# zx80_SD_12_smd_build002.net
KiCad netlist of a schematic drawn in EAGLE
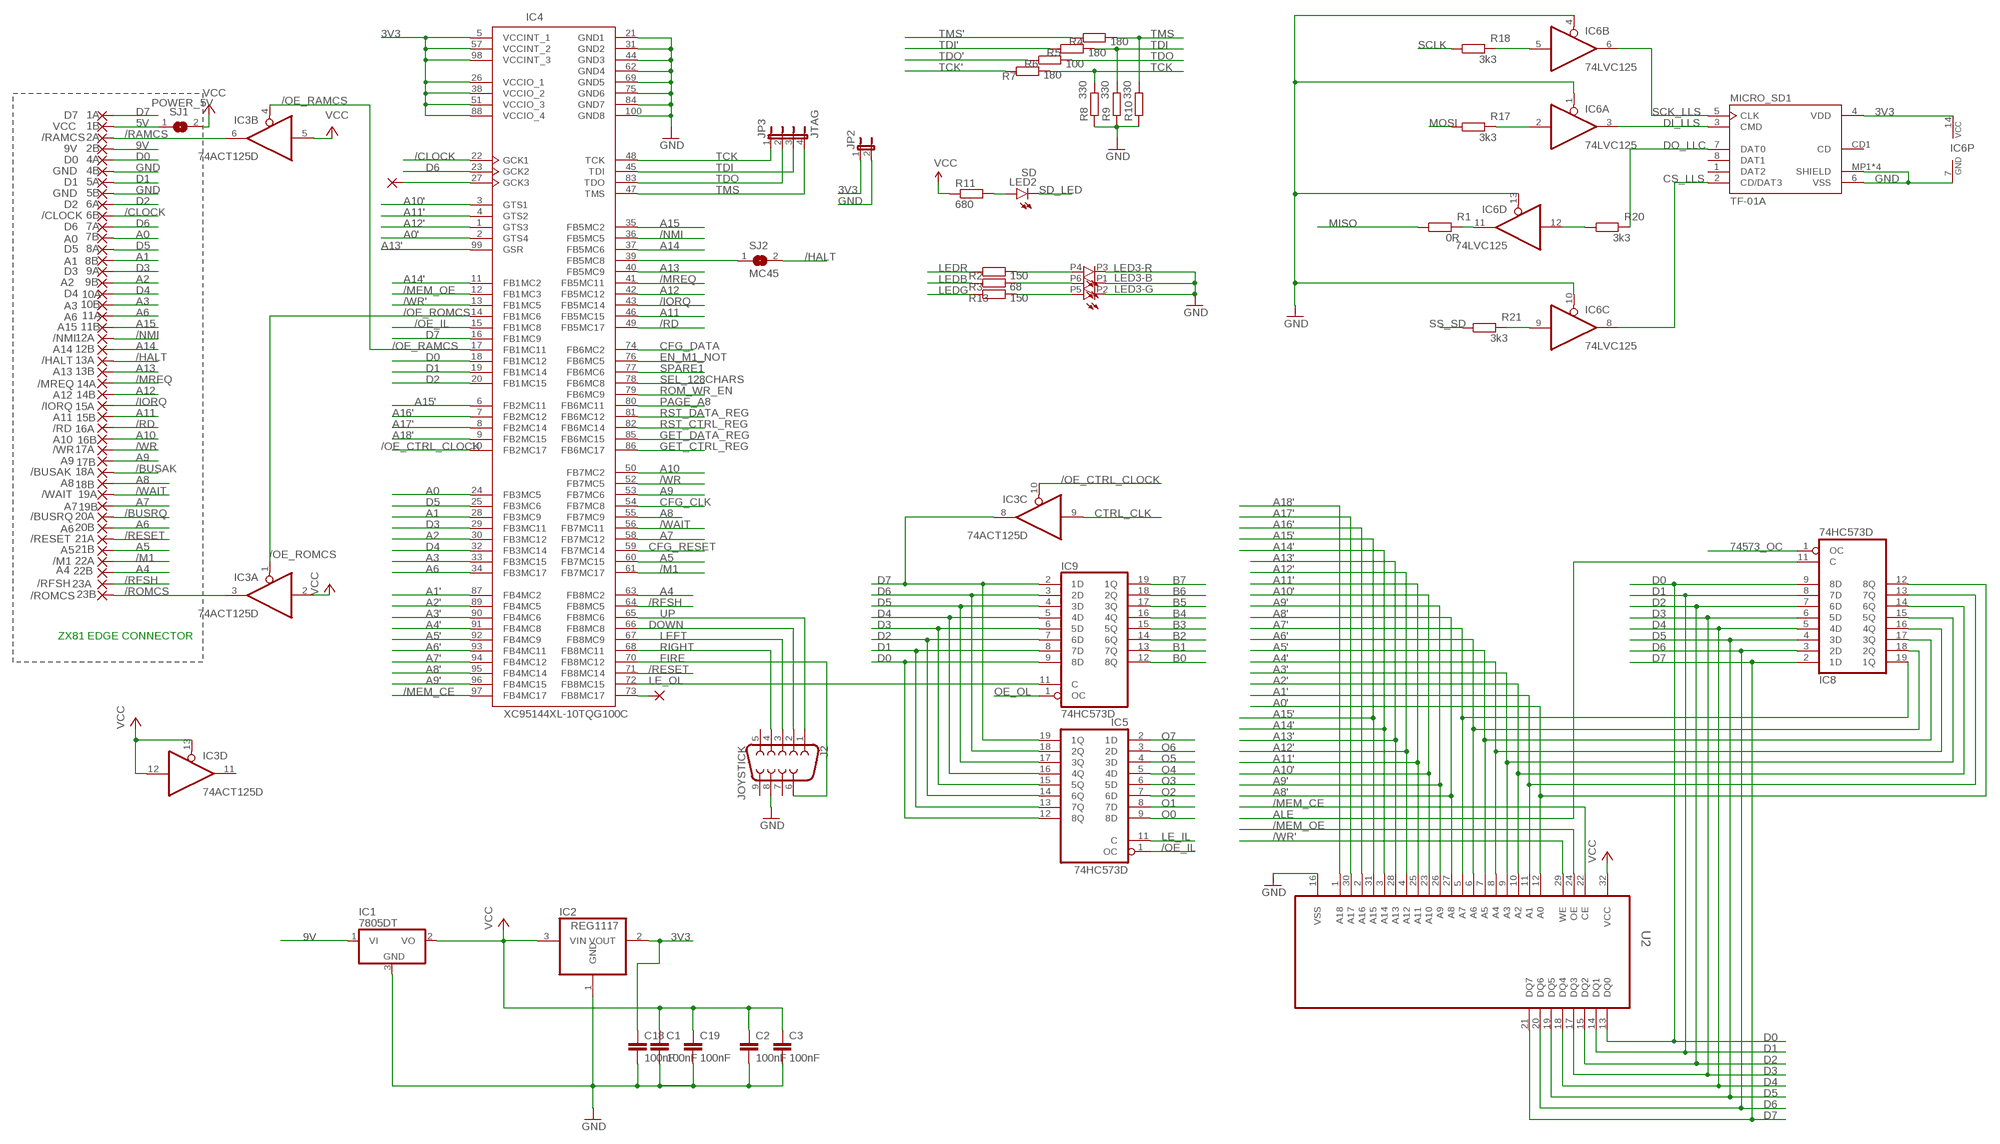
[diagram p0: schematic, sheet 1]
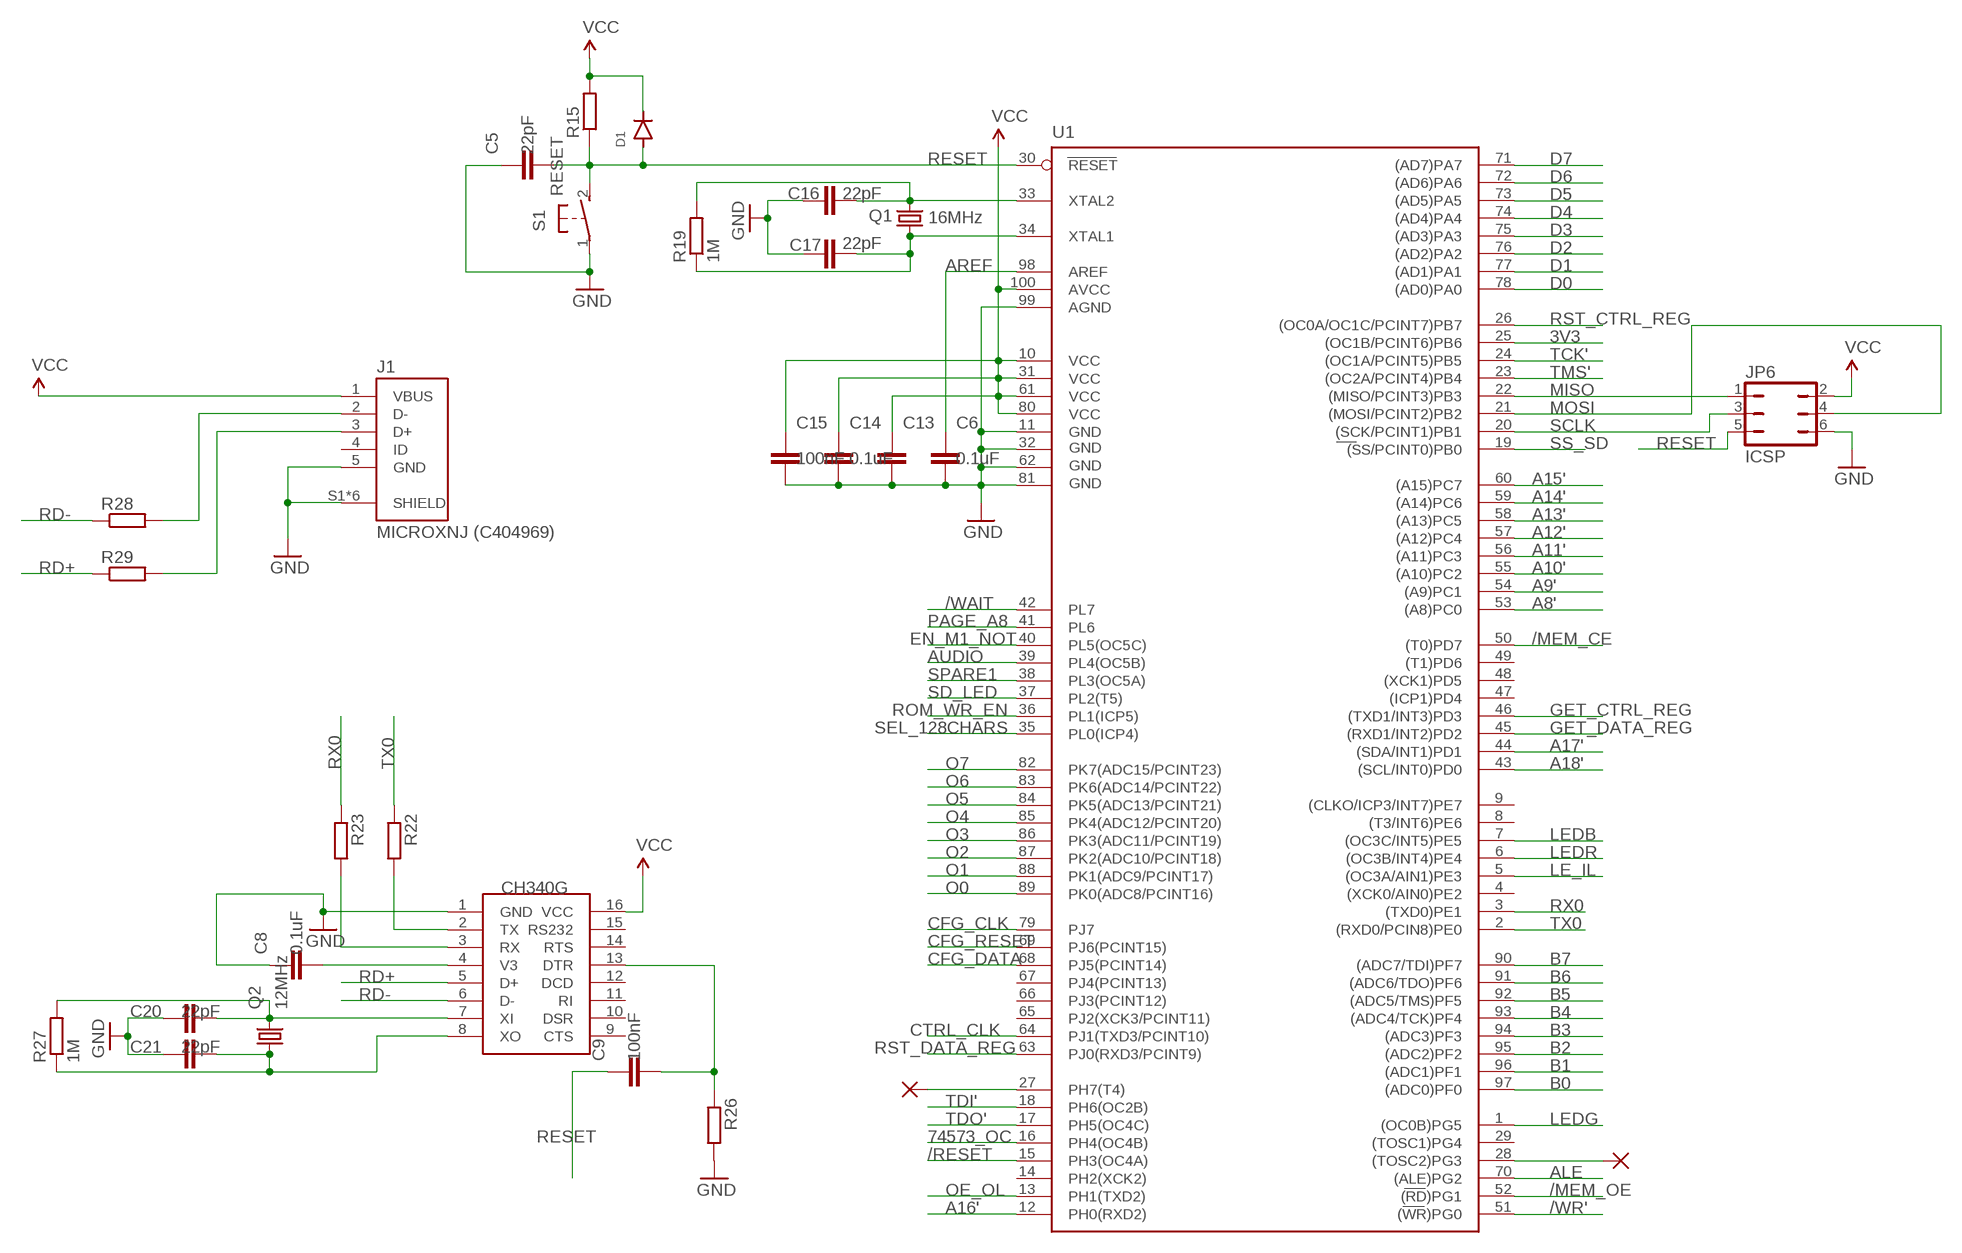
[diagram p1: schematic, sheet 2]

(export (version "E")
  (design (tool "Eeschema 10.0.6"))
  (components
    (comp (ref "C5")
      (value "22pF")
      (footprint "eagle-import:C0603")
      (libsource (lib "eagle-import") (part "C-EUC0603"))
    )
    (comp (ref "C6")
      (value "0.1uF")
      (footprint "eagle-import:C0603")
      (libsource (lib "eagle-import") (part "C-EUC0603"))
    )
    (comp (ref "C8")
      (value "0.1uF")
      (footprint "eagle-import:C0603")
      (libsource (lib "eagle-import") (part "C-EUC0603"))
    )
    (comp (ref "C9")
      (value "100nF")
      (footprint "eagle-import:C0603")
      (libsource (lib "eagle-import") (part "C-EUC0603"))
    )
    (comp (ref "C13")
      (value "0.1uF")
      (footprint "eagle-import:C0603")
      (libsource (lib "eagle-import") (part "C-EUC0603"))
    )
    (comp (ref "C14")
      (value "0.1uF")
      (footprint "eagle-import:C0603")
      (libsource (lib "eagle-import") (part "C-EUC0603"))
    )
    (comp (ref "C15")
      (value "100nF")
      (footprint "eagle-import:C0603")
      (libsource (lib "eagle-import") (part "C-EUC0603"))
    )
    (comp (ref "C16")
      (value "22pF")
      (footprint "eagle-import:C0603")
      (libsource (lib "eagle-import") (part "C-EUC0603"))
    )
    (comp (ref "C17")
      (value "22pF")
      (footprint "eagle-import:C0603")
      (libsource (lib "eagle-import") (part "C-EUC0603"))
    )
    (comp (ref "C20")
      (value "22pF")
      (footprint "eagle-import:C0603")
      (libsource (lib "eagle-import") (part "C-EUC0603"))
    )
    (comp (ref "C21")
      (value "22pF")
      (footprint "eagle-import:C0603")
      (libsource (lib "eagle-import") (part "C-EUC0603"))
    )
    (comp (ref "D1")
      (value "DIODE-SOD123")
      (footprint "eagle-import:SOD123")
      (libsource (lib "eagle-import") (part "DIODE-SOD123"))
    )
    (comp (ref "IC7")
      (value "CH340G")
      (footprint "eagle-import:SOIC16")
      (libsource (lib "eagle-import") (part "CH340G"))
    )
    (comp (ref "J1")
      (value "MICROXNJ (C404969)")
      (footprint "eagle-import:SHOUHAN_MICROXNJ")
      (fields (field (name "MF") "Shouhan") (field (name "MP") "MICROXNJ"))
      (libsource (lib "eagle-import") (part "MICROXNJ"))
    )
    (comp (ref "JP6")
      (value "ICSP")
      (footprint "eagle-import:JP3Q")
      (libsource (lib "eagle-import") (part "JP3Q"))
    )
    (comp (ref "PAD2")
      (value "1,6/0,8")
      (footprint "eagle-import:1,6_0,8")
      (libsource (lib "eagle-import") (part "1,6/0,8"))
    )
    (comp (ref "PAD3")
      (value "1,6/0,8")
      (footprint "eagle-import:1,6_0,8")
      (libsource (lib "eagle-import") (part "1,6/0,8"))
    )
    (comp (ref "Q1")
      (value "16MHz")
      (footprint "eagle-import:3.2X2.5_KX-7")
      (libsource (lib "eagle-import") (part "KX-7"))
    )
    (comp (ref "Q2")
      (value "12MHz")
      (footprint "eagle-import:3.2X2.5_KX-7")
      (libsource (lib "eagle-import") (part "KX-7"))
    )
    (comp (ref "R15")
      (value "R-EU_R0603")
      (footprint "eagle-import:R0603")
      (libsource (lib "eagle-import") (part "rcl_334_R-EU_R0603"))
    )
    (comp (ref "R19")
      (value "1M")
      (footprint "eagle-import:R0603")
      (libsource (lib "eagle-import") (part "rcl_334_R-EU_R0603"))
    )
    (comp (ref "R22")
      (value "1K")
      (footprint "eagle-import:R0603")
      (libsource (lib "eagle-import") (part "rcl_334_R-EU_R0603"))
    )
    (comp (ref "R23")
      (value "1K")
      (footprint "eagle-import:R0603")
      (libsource (lib "eagle-import") (part "rcl_334_R-EU_R0603"))
    )
    (comp (ref "R26")
      (value "1K")
      (footprint "eagle-import:R0603")
      (libsource (lib "eagle-import") (part "rcl_334_R-EU_R0603"))
    )
    (comp (ref "R27")
      (value "1M")
      (footprint "eagle-import:R0603")
      (libsource (lib "eagle-import") (part "rcl_334_R-EU_R0603"))
    )
    (comp (ref "R28")
      (value "22R")
      (footprint "eagle-import:R0603")
      (libsource (lib "eagle-import") (part "rcl_334_R-EU_R0603"))
    )
    (comp (ref "R29")
      (value "22R")
      (footprint "eagle-import:R0603")
      (libsource (lib "eagle-import") (part "rcl_334_R-EU_R0603"))
    )
    (comp (ref "S1")
      (value "RESET")
      (footprint "eagle-import:B3F-31XX")
      (fields (field (name "MPN") "B3F-3100"))
      (libsource (lib "eagle-import") (part "31-XX"))
    )
    (comp (ref "U1")
      (value "ATMEGA2560AU")
      (footprint "eagle-import:TQFP100")
      (libsource (lib "eagle-import") (part "ATMEGA2560AU"))
    )
    (comp (ref "1A")
      (value "D7")
      (footprint "eagle-import:EDGEPIN")
      (libsource (lib "eagle-import") (part "SMD2EDGEPIN"))
    )
    (comp (ref "1B")
      (value "VCC")
      (footprint "eagle-import:EDGEPIN")
      (libsource (lib "eagle-import") (part "SMD2EDGEPIN"))
    )
    (comp (ref "2A")
      (value "/RAMCS")
      (footprint "eagle-import:EDGEPIN")
      (libsource (lib "eagle-import") (part "SMD2EDGEPIN"))
    )
    (comp (ref "2B")
      (value "9V")
      (footprint "eagle-import:EDGEPIN")
      (libsource (lib "eagle-import") (part "SMD2EDGEPIN"))
    )
    (comp (ref "4A")
      (value "D0")
      (footprint "eagle-import:EDGEPIN")
      (libsource (lib "eagle-import") (part "SMD2EDGEPIN"))
    )
    (comp (ref "4B")
      (value "GND")
      (footprint "eagle-import:EDGEPIN")
      (libsource (lib "eagle-import") (part "SMD2EDGEPIN"))
    )
    (comp (ref "5A")
      (value "D1")
      (footprint "eagle-import:EDGEPIN")
      (libsource (lib "eagle-import") (part "SMD2EDGEPIN"))
    )
    (comp (ref "5B")
      (value "GND")
      (footprint "eagle-import:EDGEPIN")
      (libsource (lib "eagle-import") (part "SMD2EDGEPIN"))
    )
    (comp (ref "6A")
      (value "D2")
      (footprint "eagle-import:EDGEPIN")
      (libsource (lib "eagle-import") (part "SMD2EDGEPIN"))
    )
    (comp (ref "6B")
      (value "/CLOCK")
      (footprint "eagle-import:EDGEPIN")
      (libsource (lib "eagle-import") (part "SMD2EDGEPIN"))
    )
    (comp (ref "7A")
      (value "D6")
      (footprint "eagle-import:EDGEPIN")
      (libsource (lib "eagle-import") (part "SMD2EDGEPIN"))
    )
    (comp (ref "7B")
      (value "A0")
      (footprint "eagle-import:EDGEPIN")
      (libsource (lib "eagle-import") (part "SMD2EDGEPIN"))
    )
    (comp (ref "8A")
      (value "D5")
      (footprint "eagle-import:EDGEPIN")
      (libsource (lib "eagle-import") (part "SMD2EDGEPIN"))
    )
    (comp (ref "8B")
      (value "A1")
      (footprint "eagle-import:EDGEPIN")
      (libsource (lib "eagle-import") (part "SMD2EDGEPIN"))
    )
    (comp (ref "9A")
      (value "D3")
      (footprint "eagle-import:EDGEPIN")
      (libsource (lib "eagle-import") (part "SMD2EDGEPIN"))
    )
    (comp (ref "9B")
      (value "A2")
      (footprint "eagle-import:EDGEPIN")
      (libsource (lib "eagle-import") (part "SMD2EDGEPIN"))
    )
    (comp (ref "10A")
      (value "D4")
      (footprint "eagle-import:EDGEPIN")
      (libsource (lib "eagle-import") (part "SMD2EDGEPIN"))
    )
    (comp (ref "10B")
      (value "A3")
      (footprint "eagle-import:EDGEPIN")
      (libsource (lib "eagle-import") (part "SMD2EDGEPIN"))
    )
    (comp (ref "11A")
      (value "A6")
      (footprint "eagle-import:EDGEPIN")
      (libsource (lib "eagle-import") (part "SMD2EDGEPIN"))
    )
    (comp (ref "11B")
      (value "A15")
      (footprint "eagle-import:EDGEPIN")
      (libsource (lib "eagle-import") (part "SMD2EDGEPIN"))
    )
    (comp (ref "12A")
      (value "/NMI")
      (footprint "eagle-import:EDGEPIN")
      (libsource (lib "eagle-import") (part "SMD2EDGEPIN"))
    )
    (comp (ref "12B")
      (value "A14")
      (footprint "eagle-import:EDGEPIN")
      (libsource (lib "eagle-import") (part "SMD2EDGEPIN"))
    )
    (comp (ref "13A")
      (value "/HALT")
      (footprint "eagle-import:EDGEPIN")
      (libsource (lib "eagle-import") (part "SMD2EDGEPIN"))
    )
    (comp (ref "13B")
      (value "A13")
      (footprint "eagle-import:EDGEPIN")
      (libsource (lib "eagle-import") (part "SMD2EDGEPIN"))
    )
    (comp (ref "14A")
      (value "/MREQ")
      (footprint "eagle-import:EDGEPIN")
      (libsource (lib "eagle-import") (part "SMD2EDGEPIN"))
    )
    (comp (ref "14B")
      (value "A12")
      (footprint "eagle-import:EDGEPIN")
      (libsource (lib "eagle-import") (part "SMD2EDGEPIN"))
    )
    (comp (ref "15A")
      (value "/IORQ")
      (footprint "eagle-import:EDGEPIN")
      (libsource (lib "eagle-import") (part "SMD2EDGEPIN"))
    )
    (comp (ref "15B")
      (value "A11")
      (footprint "eagle-import:EDGEPIN")
      (libsource (lib "eagle-import") (part "SMD2EDGEPIN"))
    )
    (comp (ref "16A")
      (value "/RD")
      (footprint "eagle-import:EDGEPIN")
      (libsource (lib "eagle-import") (part "SMD2EDGEPIN"))
    )
    (comp (ref "16B")
      (value "A10")
      (footprint "eagle-import:EDGEPIN")
      (libsource (lib "eagle-import") (part "SMD2EDGEPIN"))
    )
    (comp (ref "17A")
      (value "/WR")
      (footprint "eagle-import:EDGEPIN")
      (libsource (lib "eagle-import") (part "SMD2EDGEPIN"))
    )
    (comp (ref "17B")
      (value "A9")
      (footprint "eagle-import:EDGEPIN")
      (libsource (lib "eagle-import") (part "SMD2EDGEPIN"))
    )
    (comp (ref "18A")
      (value "/BUSAK")
      (footprint "eagle-import:EDGEPIN")
      (libsource (lib "eagle-import") (part "SMD2EDGEPIN"))
    )
    (comp (ref "18B")
      (value "A8")
      (footprint "eagle-import:EDGEPIN")
      (libsource (lib "eagle-import") (part "SMD2EDGEPIN"))
    )
    (comp (ref "19A")
      (value "/WAIT")
      (footprint "eagle-import:EDGEPIN")
      (libsource (lib "eagle-import") (part "SMD2EDGEPIN"))
    )
    (comp (ref "19B")
      (value "A7")
      (footprint "eagle-import:EDGEPIN")
      (libsource (lib "eagle-import") (part "SMD2EDGEPIN"))
    )
    (comp (ref "20A")
      (value "/BUSRQ")
      (footprint "eagle-import:EDGEPIN")
      (libsource (lib "eagle-import") (part "SMD2EDGEPIN"))
    )
    (comp (ref "20B")
      (value "A6")
      (footprint "eagle-import:EDGEPIN")
      (libsource (lib "eagle-import") (part "SMD2EDGEPIN"))
    )
    (comp (ref "21A")
      (value "/RESET")
      (footprint "eagle-import:EDGEPIN")
      (libsource (lib "eagle-import") (part "SMD2EDGEPIN"))
    )
    (comp (ref "21B")
      (value "A5")
      (footprint "eagle-import:EDGEPIN")
      (libsource (lib "eagle-import") (part "SMD2EDGEPIN"))
    )
    (comp (ref "22A")
      (value "/M1")
      (footprint "eagle-import:EDGEPIN")
      (libsource (lib "eagle-import") (part "SMD2EDGEPIN"))
    )
    (comp (ref "22B")
      (value "A4")
      (footprint "eagle-import:EDGEPIN")
      (libsource (lib "eagle-import") (part "SMD2EDGEPIN"))
    )
    (comp (ref "23A")
      (value "/RFSH")
      (footprint "eagle-import:EDGEPIN")
      (libsource (lib "eagle-import") (part "SMD2EDGEPIN"))
    )
    (comp (ref "23B")
      (value "/ROMCS")
      (footprint "eagle-import:EDGEPIN")
      (libsource (lib "eagle-import") (part "SMD2EDGEPIN"))
    )
    (comp (ref "C1")
      (value "100nF")
      (footprint "eagle-import:C0603")
      (libsource (lib "eagle-import") (part "C-EUC0603"))
    )
    (comp (ref "C2")
      (value "100nF")
      (footprint "eagle-import:C0603")
      (libsource (lib "eagle-import") (part "C-EUC0603"))
    )
    (comp (ref "C3")
      (value "100nF")
      (footprint "eagle-import:C0603")
      (libsource (lib "eagle-import") (part "C-EUC0603"))
    )
    (comp (ref "C18")
      (value "100nF")
      (footprint "eagle-import:C0603")
      (libsource (lib "eagle-import") (part "C-EUC0603"))
    )
    (comp (ref "C19")
      (value "100nF")
      (footprint "eagle-import:C0603")
      (libsource (lib "eagle-import") (part "C-EUC0603"))
    )
    (comp (ref "IC1")
      (value "7805DT")
      (footprint "eagle-import:TO252")
      (libsource (lib "eagle-import") (part "78DT05"))
    )
    (comp (ref "IC2")
      (value "REG1117")
      (footprint "eagle-import:SOT223")
      (libsource (lib "eagle-import") (part "REG1117"))
    )
    (comp (ref "IC3")
      (value "74ACT125D")
      (footprint "eagle-import:SO14")
      (libsource (lib "eagle-import") (part "74125DACT"))
    )
    (comp (ref "IC4")
      (value "XC95144XL-10TQG100C")
      (footprint "eagle-import:TQFP100")
      (fields (field (name "MF") "Xilinx Inc."))
      (libsource (lib "eagle-import") (part "XC95144XL-10TQG100C"))
    )
    (comp (ref "IC5")
      (value "74HC573D")
      (footprint "eagle-import:SO20W")
      (libsource (lib "eagle-import") (part "74573DHC"))
    )
    (comp (ref "IC6")
      (value "74LVC125")
      (footprint "eagle-import:SO14")
      (libsource (lib "eagle-import") (part "74125DLS"))
    )
    (comp (ref "IC8")
      (value "74HC573D")
      (footprint "eagle-import:SO20W")
      (libsource (lib "eagle-import") (part "74573DHC"))
    )
    (comp (ref "IC9")
      (value "74HC573D")
      (footprint "eagle-import:SO20W")
      (libsource (lib "eagle-import") (part "74573DHC"))
    )
    (comp (ref "J2")
      (value "JOYSTICK")
      (footprint "eagle-import:DB9_MALE")
      (libsource (lib "eagle-import") (part "DB9MALE"))
    )
    (comp (ref "JP2")
      (value "JP1E")
      (footprint "eagle-import:JP1")
      (libsource (lib "eagle-import") (part "JP1E"))
    )
    (comp (ref "JP3")
      (value "JTAG")
      (footprint "eagle-import:JP4")
      (libsource (lib "eagle-import") (part "JP4E"))
    )
    (comp (ref "LED2")
      (value "SD")
      (footprint "eagle-import:CHIPLED_0603")
      (libsource (lib "eagle-import") (part "LEDCHIPLED_0603"))
    )
    (comp (ref "LED3")
      (value "STATUS")
      (footprint "eagle-import:3535-PLCC6")
      (libsource (lib "eagle-import") (part "3535RGB3535RGB"))
    )
    (comp (ref "MICRO_SD1")
      (value "TF-01A")
      (footprint "eagle-import:TF-01A")
      (fields (field (name "MF") "HRO Electronics Co., Ltd."))
      (libsource (lib "eagle-import") (part "TF-01A"))
    )
    (comp (ref "PAD1")
      (value "1,6/0,8")
      (footprint "eagle-import:1,6_0,8")
      (libsource (lib "eagle-import") (part "1,6/0,8"))
    )
    (comp (ref "PAD6")
      (value "P73")
      (footprint "eagle-import:1,6_0,8")
      (libsource (lib "eagle-import") (part "1,6/0,8"))
    )
    (comp (ref "R1")
      (value "0R")
      (footprint "eagle-import:R0603")
      (libsource (lib "eagle-import") (part "R-EU_R0603"))
    )
    (comp (ref "R2")
      (value "150")
      (footprint "eagle-import:R0603")
      (libsource (lib "eagle-import") (part "rcl_334_R-EU_R0603"))
    )
    (comp (ref "R3")
      (value "68")
      (footprint "eagle-import:R0603")
      (libsource (lib "eagle-import") (part "rcl_334_R-EU_R0603"))
    )
    (comp (ref "R4")
      (value "180")
      (footprint "eagle-import:R0603")
      (libsource (lib "eagle-import") (part "rcl_334_R-EU_R0603"))
    )
    (comp (ref "R5")
      (value "180")
      (footprint "eagle-import:R0603")
      (libsource (lib "eagle-import") (part "rcl_334_R-EU_R0603"))
    )
    (comp (ref "R6")
      (value "100")
      (footprint "eagle-import:R0603")
      (libsource (lib "eagle-import") (part "rcl_334_R-EU_R0603"))
    )
    (comp (ref "R7")
      (value "180")
      (footprint "eagle-import:R0603")
      (libsource (lib "eagle-import") (part "rcl_334_R-EU_R0603"))
    )
    (comp (ref "R8")
      (value "330")
      (footprint "eagle-import:R0603")
      (libsource (lib "eagle-import") (part "rcl_334_R-EU_R0603"))
    )
    (comp (ref "R9")
      (value "330")
      (footprint "eagle-import:R0603")
      (libsource (lib "eagle-import") (part "rcl_334_R-EU_R0603"))
    )
    (comp (ref "R10")
      (value "330")
      (footprint "eagle-import:R0603")
      (libsource (lib "eagle-import") (part "rcl_334_R-EU_R0603"))
    )
    (comp (ref "R11")
      (value "680")
      (footprint "eagle-import:R0603")
      (libsource (lib "eagle-import") (part "R-EU_R0603"))
    )
    (comp (ref "R13")
      (value "150")
      (footprint "eagle-import:R0603")
      (libsource (lib "eagle-import") (part "rcl_334_R-EU_R0603"))
    )
    (comp (ref "R17")
      (value "3k3")
      (footprint "eagle-import:R0603")
      (libsource (lib "eagle-import") (part "R-EU_R0603"))
    )
    (comp (ref "R18")
      (value "3k3")
      (footprint "eagle-import:R0603")
      (libsource (lib "eagle-import") (part "R-EU_R0603"))
    )
    (comp (ref "R20")
      (value "3k3")
      (footprint "eagle-import:R0603")
      (libsource (lib "eagle-import") (part "R-EU_R0603"))
    )
    (comp (ref "R21")
      (value "3k3")
      (footprint "eagle-import:R0603")
      (libsource (lib "eagle-import") (part "R-EU_R0603"))
    )
    (comp (ref "SJ1")
      (value "POWER_5V")
      (footprint "eagle-import:SJ")
      (libsource (lib "eagle-import") (part "SJ"))
    )
    (comp (ref "SJ2")
      (value "MC45")
      (footprint "eagle-import:SJ")
      (libsource (lib "eagle-import") (part "SJ"))
    )
    (comp (ref "U2")
      (value "AS6C4008-55SINSOP5")
      (footprint "eagle-import:SOP32-5")
      (libsource (lib "eagle-import") (part "AS6C4008-55SINSOP5"))
    )
  )
  (nets
    (net (code "1") (name "3V3") (class "Default")
      (node (ref "C18") (pin "1") (pinfunction "1_1") (pintype "passive"))
      (node (ref "IC2") (pin "2") (pinfunction "VOUT_2") (pintype "output"))
      (node (ref "IC4") (pin "26") (pinfunction "VCCIO_1_26") (pintype "power_in"))
      (node (ref "IC4") (pin "38") (pinfunction "VCCIO_2_38") (pintype "power_in"))
      (node (ref "IC4") (pin "5") (pinfunction "VCCINT_1_5") (pintype "power_in"))
      (node (ref "IC4") (pin "51") (pinfunction "VCCIO_3_51") (pintype "power_in"))
      (node (ref "IC4") (pin "57") (pinfunction "VCCINT_2_57") (pintype "power_in"))
      (node (ref "IC4") (pin "88") (pinfunction "VCCIO_4_88") (pintype "power_in"))
      (node (ref "IC4") (pin "98") (pinfunction "VCCINT_3_98") (pintype "power_in"))
      (node (ref "IC6") (pin "14") (pinfunction "VCC_14") (pintype "power_in"))
      (node (ref "JP2") (pin "1") (pinfunction "1_1") (pintype "passive"))
      (node (ref "MICRO_SD1") (pin "4") (pinfunction "VDD_4") (pintype "power_in"))
      (node (ref "U1") (pin "25") (pinfunction "(OC1B/PCINT6)PB6_25") (pintype "bidirectional"))
    )
    (net (code "2") (name "5V") (class "Default")
      (node (ref "1B") (pin "1") (pinfunction "P_1") (pintype "passive"))
      (node (ref "SJ1") (pin "1") (pinfunction "1_1") (pintype "passive"))
    )
    (net (code "3") (name "9V") (class "Default")
      (node (ref "2B") (pin "1") (pinfunction "P_1") (pintype "passive"))
      (node (ref "IC1") (pin "1") (pinfunction "VI_1") (pintype "input"))
    )
    (net (code "4") (name "74573_OC") (class "Default")
      (node (ref "IC8") (pin "1") (pinfunction "OC_1") (pintype "input"))
      (node (ref "U1") (pin "16") (pinfunction "PH4(OC4B)_16") (pintype "bidirectional"))
    )
    (net (code "5") (name "A0") (class "Default")
      (node (ref "7B") (pin "1") (pinfunction "P_1") (pintype "passive"))
      (node (ref "IC4") (pin "24") (pinfunction "FB3MC5_24") (pintype "bidirectional"))
    )
    (net (code "6") (name "A0'") (class "Default")
      (node (ref "IC4") (pin "2") (pinfunction "GTS4_2") (pintype "bidirectional"))
      (node (ref "IC8") (pin "12") (pinfunction "8Q_12") (pintype "tri_state"))
      (node (ref "U2") (pin "12") (pinfunction "A0_12") (pintype "input"))
    )
    (net (code "7") (name "A1") (class "Default")
      (node (ref "8B") (pin "1") (pinfunction "P_1") (pintype "passive"))
      (node (ref "IC4") (pin "28") (pinfunction "FB3MC9_28") (pintype "bidirectional"))
    )
    (net (code "8") (name "A1'") (class "Default")
      (node (ref "IC4") (pin "87") (pinfunction "FB4MC2_87") (pintype "bidirectional"))
      (node (ref "IC8") (pin "13") (pinfunction "7Q_13") (pintype "tri_state"))
      (node (ref "U2") (pin "11") (pinfunction "A1_11") (pintype "input"))
    )
    (net (code "9") (name "A2") (class "Default")
      (node (ref "9B") (pin "1") (pinfunction "P_1") (pintype "passive"))
      (node (ref "IC4") (pin "30") (pinfunction "FB3MC12_30") (pintype "bidirectional"))
    )
    (net (code "10") (name "A2'") (class "Default")
      (node (ref "IC4") (pin "89") (pinfunction "FB4MC5_89") (pintype "bidirectional"))
      (node (ref "IC8") (pin "14") (pinfunction "6Q_14") (pintype "tri_state"))
      (node (ref "U2") (pin "10") (pinfunction "A2_10") (pintype "input"))
    )
    (net (code "11") (name "A3") (class "Default")
      (node (ref "10B") (pin "1") (pinfunction "P_1") (pintype "passive"))
      (node (ref "IC4") (pin "33") (pinfunction "FB3MC15_33") (pintype "bidirectional"))
    )
    (net (code "12") (name "A3'") (class "Default")
      (node (ref "IC4") (pin "90") (pinfunction "FB4MC6_90") (pintype "bidirectional"))
      (node (ref "IC8") (pin "15") (pinfunction "5Q_15") (pintype "tri_state"))
      (node (ref "U2") (pin "9") (pinfunction "A3_9") (pintype "input"))
    )
    (net (code "13") (name "A4") (class "Default")
      (node (ref "22B") (pin "1") (pinfunction "P_1") (pintype "passive"))
      (node (ref "IC4") (pin "63") (pinfunction "FB8MC2_63") (pintype "bidirectional"))
    )
    (net (code "14") (name "A4'") (class "Default")
      (node (ref "IC4") (pin "91") (pinfunction "FB4MC8_91") (pintype "bidirectional"))
      (node (ref "IC8") (pin "16") (pinfunction "4Q_16") (pintype "tri_state"))
      (node (ref "U2") (pin "8") (pinfunction "A4_8") (pintype "input"))
    )
    (net (code "15") (name "A5") (class "Default")
      (node (ref "21B") (pin "1") (pinfunction "P_1") (pintype "passive"))
      (node (ref "IC4") (pin "60") (pinfunction "FB7MC15_60") (pintype "bidirectional"))
    )
    (net (code "16") (name "A5'") (class "Default")
      (node (ref "IC4") (pin "92") (pinfunction "FB4MC9_92") (pintype "bidirectional"))
      (node (ref "IC8") (pin "17") (pinfunction "3Q_17") (pintype "tri_state"))
      (node (ref "U2") (pin "7") (pinfunction "A5_7") (pintype "input"))
    )
    (net (code "17") (name "A6") (class "Default")
      (node (ref "11A") (pin "1") (pinfunction "P_1") (pintype "passive"))
      (node (ref "20B") (pin "1") (pinfunction "P_1") (pintype "passive"))
      (node (ref "IC4") (pin "34") (pinfunction "FB3MC17_34") (pintype "bidirectional"))
    )
    (net (code "18") (name "A6'") (class "Default")
      (node (ref "IC4") (pin "93") (pinfunction "FB4MC11_93") (pintype "bidirectional"))
      (node (ref "IC8") (pin "18") (pinfunction "2Q_18") (pintype "tri_state"))
      (node (ref "U2") (pin "6") (pinfunction "A6_6") (pintype "input"))
    )
    (net (code "19") (name "A7") (class "Default")
      (node (ref "19B") (pin "1") (pinfunction "P_1") (pintype "passive"))
      (node (ref "IC4") (pin "58") (pinfunction "FB7MC12_58") (pintype "bidirectional"))
    )
    (net (code "20") (name "A7'") (class "Default")
      (node (ref "IC4") (pin "94") (pinfunction "FB4MC12_94") (pintype "bidirectional"))
      (node (ref "IC8") (pin "19") (pinfunction "1Q_19") (pintype "tri_state"))
      (node (ref "U2") (pin "5") (pinfunction "A7_5") (pintype "input"))
    )
    (net (code "21") (name "A8") (class "Default")
      (node (ref "18B") (pin "1") (pinfunction "P_1") (pintype "passive"))
      (node (ref "IC4") (pin "55") (pinfunction "FB7MC9_55") (pintype "bidirectional"))
    )
    (net (code "22") (name "A8'") (class "Default")
      (node (ref "IC4") (pin "95") (pinfunction "FB4MC14_95") (pintype "bidirectional"))
      (node (ref "U1") (pin "53") (pinfunction "(A8)PC0_53") (pintype "bidirectional"))
      (node (ref "U2") (pin "27") (pinfunction "A8_27") (pintype "input"))
    )
    (net (code "23") (name "A9") (class "Default")
      (node (ref "17B") (pin "1") (pinfunction "P_1") (pintype "passive"))
      (node (ref "IC4") (pin "53") (pinfunction "FB7MC6_53") (pintype "bidirectional"))
    )
    (net (code "24") (name "A9'") (class "Default")
      (node (ref "IC4") (pin "96") (pinfunction "FB4MC15_96") (pintype "bidirectional"))
      (node (ref "U1") (pin "54") (pinfunction "(A9)PC1_54") (pintype "bidirectional"))
      (node (ref "U2") (pin "26") (pinfunction "A9_26") (pintype "input"))
    )
    (net (code "25") (name "A10") (class "Default")
      (node (ref "16B") (pin "1") (pinfunction "P_1") (pintype "passive"))
      (node (ref "IC4") (pin "50") (pinfunction "FB7MC2_50") (pintype "bidirectional"))
    )
    (net (code "26") (name "A10'") (class "Default")
      (node (ref "IC4") (pin "3") (pinfunction "GTS1_3") (pintype "bidirectional"))
      (node (ref "U1") (pin "55") (pinfunction "(A10)PC2_55") (pintype "bidirectional"))
      (node (ref "U2") (pin "23") (pinfunction "A10_23") (pintype "input"))
    )
    (net (code "27") (name "A11") (class "Default")
      (node (ref "15B") (pin "1") (pinfunction "P_1") (pintype "passive"))
      (node (ref "IC4") (pin "46") (pinfunction "FB5MC15_46") (pintype "bidirectional"))
    )
    (net (code "28") (name "A11'") (class "Default")
      (node (ref "IC4") (pin "4") (pinfunction "GTS2_4") (pintype "bidirectional"))
      (node (ref "U1") (pin "56") (pinfunction "(A11)PC3_56") (pintype "bidirectional"))
      (node (ref "U2") (pin "25") (pinfunction "A11_25") (pintype "input"))
    )
    (net (code "29") (name "A12") (class "Default")
      (node (ref "14B") (pin "1") (pinfunction "P_1") (pintype "passive"))
      (node (ref "IC4") (pin "42") (pinfunction "FB5MC12_42") (pintype "bidirectional"))
    )
    (net (code "30") (name "A12'") (class "Default")
      (node (ref "IC4") (pin "1") (pinfunction "GTS3_1") (pintype "bidirectional"))
      (node (ref "U1") (pin "57") (pinfunction "(A12)PC4_57") (pintype "bidirectional"))
      (node (ref "U2") (pin "4") (pinfunction "A12_4") (pintype "input"))
    )
    (net (code "31") (name "A13") (class "Default")
      (node (ref "13B") (pin "1") (pinfunction "P_1") (pintype "passive"))
      (node (ref "IC4") (pin "40") (pinfunction "FB5MC9_40") (pintype "bidirectional"))
    )
    (net (code "32") (name "A13'") (class "Default")
      (node (ref "IC4") (pin "99") (pinfunction "GSR_99") (pintype "bidirectional"))
      (node (ref "U1") (pin "58") (pinfunction "(A13)PC5_58") (pintype "bidirectional"))
      (node (ref "U2") (pin "28") (pinfunction "A13_28") (pintype "input"))
    )
    (net (code "33") (name "A14") (class "Default")
      (node (ref "12B") (pin "1") (pinfunction "P_1") (pintype "passive"))
      (node (ref "IC4") (pin "37") (pinfunction "FB5MC6_37") (pintype "bidirectional"))
    )
    (net (code "34") (name "A14'") (class "Default")
      (node (ref "IC4") (pin "11") (pinfunction "FB1MC2_11") (pintype "bidirectional"))
      (node (ref "U1") (pin "59") (pinfunction "(A14)PC6_59") (pintype "bidirectional"))
      (node (ref "U2") (pin "3") (pinfunction "A14_3") (pintype "input"))
    )
    (net (code "35") (name "A15") (class "Default")
      (node (ref "11B") (pin "1") (pinfunction "P_1") (pintype "passive"))
      (node (ref "IC4") (pin "35") (pinfunction "FB5MC2_35") (pintype "bidirectional"))
    )
    (net (code "36") (name "A15'") (class "Default")
      (node (ref "IC4") (pin "6") (pinfunction "FB2MC11_6") (pintype "bidirectional"))
      (node (ref "U1") (pin "60") (pinfunction "(A15)PC7_60") (pintype "bidirectional"))
      (node (ref "U2") (pin "31") (pinfunction "A15_31") (pintype "input"))
    )
    (net (code "37") (name "A16'") (class "Default")
      (node (ref "IC4") (pin "7") (pinfunction "FB2MC12_7") (pintype "bidirectional"))
      (node (ref "U1") (pin "12") (pinfunction "PH0(RXD2)_12") (pintype "bidirectional"))
      (node (ref "U2") (pin "2") (pinfunction "A16_2") (pintype "input"))
    )
    (net (code "38") (name "A17'") (class "Default")
      (node (ref "IC4") (pin "8") (pinfunction "FB2MC14_8") (pintype "bidirectional"))
      (node (ref "U1") (pin "44") (pinfunction "(SDA/INT1)PD1_44") (pintype "bidirectional"))
      (node (ref "U2") (pin "30") (pinfunction "A17_30") (pintype "input"))
    )
    (net (code "39") (name "A18'") (class "Default")
      (node (ref "IC4") (pin "9") (pinfunction "FB2MC15_9") (pintype "bidirectional"))
      (node (ref "U1") (pin "43") (pinfunction "(SCL/INT0)PD0_43") (pintype "bidirectional"))
      (node (ref "U2") (pin "1") (pinfunction "A18_1") (pintype "input"))
    )
    (net (code "40") (name "ALE") (class "Default")
      (node (ref "IC8") (pin "11") (pinfunction "C_11") (pintype "input"))
      (node (ref "U1") (pin "70") (pinfunction "(ALE)PG2_70") (pintype "bidirectional"))
    )
    (net (code "41") (name "AREF") (class "Default")
      (node (ref "C6") (pin "1") (pinfunction "1_1") (pintype "passive"))
      (node (ref "U1") (pin "98") (pinfunction "AREF_98") (pintype "bidirectional"))
    )
    (net (code "42") (name "AUDIO") (class "Default")
      (node (ref "U1") (pin "39") (pinfunction "PL4(OC5B)_39") (pintype "bidirectional"))
    )
    (net (code "43") (name "B0") (class "Default")
      (node (ref "IC9") (pin "12") (pinfunction "8Q_12") (pintype "tri_state"))
      (node (ref "U1") (pin "97") (pinfunction "(ADC0)PF0_97") (pintype "bidirectional"))
    )
    (net (code "44") (name "B1") (class "Default")
      (node (ref "IC9") (pin "13") (pinfunction "7Q_13") (pintype "tri_state"))
      (node (ref "U1") (pin "96") (pinfunction "(ADC1)PF1_96") (pintype "bidirectional"))
    )
    (net (code "45") (name "B2") (class "Default")
      (node (ref "IC9") (pin "14") (pinfunction "6Q_14") (pintype "tri_state"))
      (node (ref "U1") (pin "95") (pinfunction "(ADC2)PF2_95") (pintype "bidirectional"))
    )
    (net (code "46") (name "B3") (class "Default")
      (node (ref "IC9") (pin "15") (pinfunction "5Q_15") (pintype "tri_state"))
      (node (ref "U1") (pin "94") (pinfunction "(ADC3)PF3_94") (pintype "bidirectional"))
    )
    (net (code "47") (name "B4") (class "Default")
      (node (ref "IC9") (pin "16") (pinfunction "4Q_16") (pintype "tri_state"))
      (node (ref "U1") (pin "93") (pinfunction "(ADC4/TCK)PF4_93") (pintype "bidirectional"))
    )
    (net (code "48") (name "B5") (class "Default")
      (node (ref "IC9") (pin "17") (pinfunction "3Q_17") (pintype "tri_state"))
      (node (ref "U1") (pin "92") (pinfunction "(ADC5/TMS)PF5_92") (pintype "bidirectional"))
    )
    (net (code "49") (name "B6") (class "Default")
      (node (ref "IC9") (pin "18") (pinfunction "2Q_18") (pintype "tri_state"))
      (node (ref "U1") (pin "91") (pinfunction "(ADC6/TDO)PF6_91") (pintype "bidirectional"))
    )
    (net (code "50") (name "B7") (class "Default")
      (node (ref "IC9") (pin "19") (pinfunction "1Q_19") (pintype "tri_state"))
      (node (ref "U1") (pin "90") (pinfunction "(ADC7/TDI)PF7_90") (pintype "bidirectional"))
    )
    (net (code "51") (name "CFG_CLK") (class "Default")
      (node (ref "IC4") (pin "54") (pinfunction "FB7MC8_54") (pintype "bidirectional"))
      (node (ref "U1") (pin "79") (pinfunction "PJ7_79") (pintype "bidirectional"))
    )
    (net (code "52") (name "CFG_DATA") (class "Default")
      (node (ref "IC4") (pin "74") (pinfunction "FB6MC2_74") (pintype "bidirectional"))
      (node (ref "U1") (pin "68") (pinfunction "PJ5(PCINT14)_68") (pintype "bidirectional"))
    )
    (net (code "53") (name "CFG_RESET") (class "Default")
      (node (ref "IC4") (pin "59") (pinfunction "FB7MC14_59") (pintype "bidirectional"))
      (node (ref "U1") (pin "69") (pinfunction "PJ6(PCINT15)_69") (pintype "bidirectional"))
    )
    (net (code "54") (name "CS_LLS") (class "Default")
      (node (ref "IC6") (pin "8") (pinfunction "O_8") (pintype "tri_state"))
      (node (ref "MICRO_SD1") (pin "2") (pinfunction "CD/DAT3_2") (pintype "bidirectional"))
    )
    (net (code "55") (name "CTRL_CLK") (class "Default")
      (node (ref "IC3") (pin "9") (pinfunction "I_9") (pintype "input"))
      (node (ref "U1") (pin "64") (pinfunction "PJ1(TXD3/PCINT10)_64") (pintype "bidirectional"))
    )
    (net (code "56") (name "D0") (class "Default")
      (node (ref "4A") (pin "1") (pinfunction "P_1") (pintype "passive"))
      (node (ref "IC4") (pin "18") (pinfunction "FB1MC12_18") (pintype "bidirectional"))
      (node (ref "IC5") (pin "12") (pinfunction "8Q_12") (pintype "tri_state"))
      (node (ref "IC8") (pin "9") (pinfunction "8D_9") (pintype "input"))
      (node (ref "IC9") (pin "9") (pinfunction "8D_9") (pintype "input"))
      (node (ref "U1") (pin "78") (pinfunction "(AD0)PA0_78") (pintype "bidirectional"))
      (node (ref "U2") (pin "13") (pinfunction "DQ0_13") (pintype "output"))
    )
    (net (code "57") (name "D1") (class "Default")
      (node (ref "5A") (pin "1") (pinfunction "P_1") (pintype "passive"))
      (node (ref "IC4") (pin "19") (pinfunction "FB1MC14_19") (pintype "bidirectional"))
      (node (ref "IC5") (pin "13") (pinfunction "7Q_13") (pintype "tri_state"))
      (node (ref "IC8") (pin "8") (pinfunction "7D_8") (pintype "input"))
      (node (ref "IC9") (pin "8") (pinfunction "7D_8") (pintype "input"))
      (node (ref "U1") (pin "77") (pinfunction "(AD1)PA1_77") (pintype "bidirectional"))
      (node (ref "U2") (pin "14") (pinfunction "DQ1_14") (pintype "output"))
    )
    (net (code "58") (name "D2") (class "Default")
      (node (ref "6A") (pin "1") (pinfunction "P_1") (pintype "passive"))
      (node (ref "IC4") (pin "20") (pinfunction "FB1MC15_20") (pintype "bidirectional"))
      (node (ref "IC5") (pin "14") (pinfunction "6Q_14") (pintype "tri_state"))
      (node (ref "IC8") (pin "7") (pinfunction "6D_7") (pintype "input"))
      (node (ref "IC9") (pin "7") (pinfunction "6D_7") (pintype "input"))
      (node (ref "U1") (pin "76") (pinfunction "(AD2)PA2_76") (pintype "bidirectional"))
      (node (ref "U2") (pin "15") (pinfunction "DQ2_15") (pintype "output"))
    )
    (net (code "59") (name "D3") (class "Default")
      (node (ref "9A") (pin "1") (pinfunction "P_1") (pintype "passive"))
      (node (ref "IC4") (pin "29") (pinfunction "FB3MC11_29") (pintype "bidirectional"))
      (node (ref "IC5") (pin "15") (pinfunction "5Q_15") (pintype "tri_state"))
      (node (ref "IC8") (pin "6") (pinfunction "5D_6") (pintype "input"))
      (node (ref "IC9") (pin "6") (pinfunction "5D_6") (pintype "input"))
      (node (ref "U1") (pin "75") (pinfunction "(AD3)PA3_75") (pintype "bidirectional"))
      (node (ref "U2") (pin "17") (pinfunction "DQ3_17") (pintype "output"))
    )
    (net (code "60") (name "D4") (class "Default")
      (node (ref "10A") (pin "1") (pinfunction "P_1") (pintype "passive"))
      (node (ref "IC4") (pin "32") (pinfunction "FB3MC14_32") (pintype "bidirectional"))
      (node (ref "IC5") (pin "16") (pinfunction "4Q_16") (pintype "tri_state"))
      (node (ref "IC8") (pin "5") (pinfunction "4D_5") (pintype "input"))
      (node (ref "IC9") (pin "5") (pinfunction "4D_5") (pintype "input"))
      (node (ref "U1") (pin "74") (pinfunction "(AD4)PA4_74") (pintype "bidirectional"))
      (node (ref "U2") (pin "18") (pinfunction "DQ4_18") (pintype "output"))
    )
    (net (code "61") (name "D5") (class "Default")
      (node (ref "8A") (pin "1") (pinfunction "P_1") (pintype "passive"))
      (node (ref "IC4") (pin "25") (pinfunction "FB3MC6_25") (pintype "bidirectional"))
      (node (ref "IC5") (pin "17") (pinfunction "3Q_17") (pintype "tri_state"))
      (node (ref "IC8") (pin "4") (pinfunction "3D_4") (pintype "input"))
      (node (ref "IC9") (pin "4") (pinfunction "3D_4") (pintype "input"))
      (node (ref "U1") (pin "73") (pinfunction "(AD5)PA5_73") (pintype "bidirectional"))
      (node (ref "U2") (pin "19") (pinfunction "DQ5_19") (pintype "output"))
    )
    (net (code "62") (name "D6") (class "Default")
      (node (ref "7A") (pin "1") (pinfunction "P_1") (pintype "passive"))
      (node (ref "IC4") (pin "23") (pinfunction "GCK2_23") (pintype "bidirectional"))
      (node (ref "IC5") (pin "18") (pinfunction "2Q_18") (pintype "tri_state"))
      (node (ref "IC8") (pin "3") (pinfunction "2D_3") (pintype "input"))
      (node (ref "IC9") (pin "3") (pinfunction "2D_3") (pintype "input"))
      (node (ref "U1") (pin "72") (pinfunction "(AD6)PA6_72") (pintype "bidirectional"))
      (node (ref "U2") (pin "20") (pinfunction "DQ6_20") (pintype "output"))
    )
    (net (code "63") (name "D7") (class "Default")
      (node (ref "1A") (pin "1") (pinfunction "P_1") (pintype "passive"))
      (node (ref "IC3") (pin "8") (pinfunction "O_8") (pintype "tri_state"))
      (node (ref "IC4") (pin "16") (pinfunction "FB1MC9_16") (pintype "bidirectional"))
      (node (ref "IC5") (pin "19") (pinfunction "1Q_19") (pintype "tri_state"))
      (node (ref "IC8") (pin "2") (pinfunction "1D_2") (pintype "input"))
      (node (ref "IC9") (pin "2") (pinfunction "1D_2") (pintype "input"))
      (node (ref "U1") (pin "71") (pinfunction "(AD7)PA7_71") (pintype "bidirectional"))
      (node (ref "U2") (pin "21") (pinfunction "DQ7_21") (pintype "output"))
    )
    (net (code "64") (name "DI_LLS") (class "Default")
      (node (ref "IC6") (pin "3") (pinfunction "O_3") (pintype "tri_state"))
      (node (ref "MICRO_SD1") (pin "3") (pinfunction "CMD_3") (pintype "bidirectional"))
    )
    (net (code "65") (name "DOWN") (class "Default")
      (node (ref "IC4") (pin "66") (pinfunction "FB8MC8_66") (pintype "bidirectional"))
      (node (ref "J2") (pin "2") (pinfunction "2_2") (pintype "passive"))
    )
    (net (code "66") (name "DO_LLC") (class "Default")
      (node (ref "IC6") (pin "12") (pinfunction "I_12") (pintype "input"))
      (node (ref "R20") (pin "1") (pinfunction "1_1") (pintype "passive"))
    )
    (net (code "67") (name "EN_M1_NOT") (class "Default")
      (node (ref "IC4") (pin "76") (pinfunction "FB6MC5_76") (pintype "bidirectional"))
      (node (ref "U1") (pin "40") (pinfunction "PL5(OC5C)_40") (pintype "bidirectional"))
    )
    (net (code "68") (name "FIRE") (class "Default")
      (node (ref "IC4") (pin "70") (pinfunction "FB8MC12_70") (pintype "bidirectional"))
      (node (ref "J2") (pin "6") (pinfunction "6_6") (pintype "passive"))
    )
    (net (code "69") (name "GET_CTRL_REG") (class "Default")
      (node (ref "IC4") (pin "86") (pinfunction "FB6MC17_86") (pintype "bidirectional"))
      (node (ref "U1") (pin "46") (pinfunction "(TXD1/INT3)PD3_46") (pintype "bidirectional"))
    )
    (net (code "70") (name "GET_DATA_REG") (class "Default")
      (node (ref "IC4") (pin "85") (pinfunction "FB6MC15_85") (pintype "bidirectional"))
      (node (ref "U1") (pin "45") (pinfunction "(RXD1/INT2)PD2_45") (pintype "bidirectional"))
    )
    (net (code "71") (name "GND") (class "Default")
      (node (ref "4B") (pin "1") (pinfunction "P_1") (pintype "passive"))
      (node (ref "5B") (pin "1") (pinfunction "P_1") (pintype "passive"))
      (node (ref "C1") (pin "2") (pinfunction "2_2") (pintype "passive"))
      (node (ref "C13") (pin "2") (pinfunction "2_2") (pintype "passive"))
      (node (ref "C14") (pin "2") (pinfunction "2_2") (pintype "passive"))
      (node (ref "C15") (pin "2") (pinfunction "2_2") (pintype "passive"))
      (node (ref "C16") (pin "1") (pinfunction "1_1") (pintype "passive"))
      (node (ref "C17") (pin "1") (pinfunction "1_1") (pintype "passive"))
      (node (ref "C18") (pin "2") (pinfunction "2_2") (pintype "passive"))
      (node (ref "C19") (pin "2") (pinfunction "2_2") (pintype "passive"))
      (node (ref "C2") (pin "2") (pinfunction "2_2") (pintype "passive"))
      (node (ref "C20") (pin "1") (pinfunction "1_1") (pintype "passive"))
      (node (ref "C21") (pin "1") (pinfunction "1_1") (pintype "passive"))
      (node (ref "C3") (pin "2") (pinfunction "2_2") (pintype "passive"))
      (node (ref "C5") (pin "1") (pinfunction "1_1") (pintype "passive"))
      (node (ref "C6") (pin "2") (pinfunction "2_2") (pintype "passive"))
      (node (ref "C8") (pin "1") (pinfunction "1_1") (pintype "passive"))
      (node (ref "IC1") (pin "3") (pinfunction "GND_3") (pintype "passive"))
      (node (ref "IC2") (pin "1") (pinfunction "GND_1") (pintype "power_in"))
      (node (ref "IC4") (pin "100") (pinfunction "GND8_100") (pintype "power_in"))
      (node (ref "IC4") (pin "21") (pinfunction "GND1_21") (pintype "power_in"))
      (node (ref "IC4") (pin "31") (pinfunction "GND2_31") (pintype "power_in"))
      (node (ref "IC4") (pin "44") (pinfunction "GND3_44") (pintype "power_in"))
      (node (ref "IC4") (pin "62") (pinfunction "GND4_62") (pintype "power_in"))
      (node (ref "IC4") (pin "69") (pinfunction "GND5_69") (pintype "power_in"))
      (node (ref "IC4") (pin "75") (pinfunction "GND6_75") (pintype "power_in"))
      (node (ref "IC4") (pin "84") (pinfunction "GND7_84") (pintype "power_in"))
      (node (ref "IC6") (pin "1") (pinfunction "OE_1") (pintype "input"))
      (node (ref "IC6") (pin "10") (pinfunction "OE_10") (pintype "input"))
      (node (ref "IC6") (pin "13") (pinfunction "OE_13") (pintype "input"))
      (node (ref "IC6") (pin "4") (pinfunction "OE_4") (pintype "input"))
      (node (ref "IC6") (pin "7") (pinfunction "GND_7") (pintype "power_in"))
      (node (ref "IC7") (pin "1") (pinfunction "GND_1") (pintype "bidirectional"))
      (node (ref "J1") (pin "5") (pinfunction "GND_5") (pintype "power_in"))
      (node (ref "J1") (pin "S1") (pinfunction "SHIELD_S1") (pintype "passive"))
      (node (ref "J1") (pin "S2") (pinfunction "SHIELD_S2") (pintype "passive"))
      (node (ref "J1") (pin "S3") (pinfunction "SHIELD_S3") (pintype "passive"))
      (node (ref "J1") (pin "S4") (pinfunction "SHIELD_S4") (pintype "passive"))
      (node (ref "J1") (pin "S5") (pinfunction "SHIELD_S5") (pintype "passive"))
      (node (ref "J1") (pin "S6") (pinfunction "SHIELD_S6") (pintype "passive"))
      (node (ref "J2") (pin "8") (pinfunction "8_8") (pintype "passive"))
      (node (ref "JP2") (pin "2") (pinfunction "2_2") (pintype "passive"))
      (node (ref "JP6") (pin "6") (pinfunction "6_6") (pintype "passive"))
      (node (ref "LED3") (pin "P1") (pinfunction "C_P1") (pintype "passive"))
      (node (ref "LED3") (pin "P2") (pinfunction "C_P2") (pintype "passive"))
      (node (ref "LED3") (pin "P3") (pinfunction "C_P3") (pintype "passive"))
      (node (ref "MICRO_SD1") (pin "6") (pinfunction "VSS_6") (pintype "power_in"))
      (node (ref "MICRO_SD1") (pin "MP1") (pinfunction "SHIELD_MP1") (pintype "power_in"))
      (node (ref "MICRO_SD1") (pin "MP2") (pinfunction "SHIELD_MP2") (pintype "power_in"))
      (node (ref "MICRO_SD1") (pin "MP3") (pinfunction "SHIELD_MP3") (pintype "power_in"))
      (node (ref "MICRO_SD1") (pin "MP4") (pinfunction "SHIELD_MP4") (pintype "power_in"))
      (node (ref "R10") (pin "1") (pinfunction "1_1") (pintype "passive"))
      (node (ref "R26") (pin "2") (pinfunction "2_2") (pintype "passive"))
      (node (ref "R8") (pin "1") (pinfunction "1_1") (pintype "passive"))
      (node (ref "R9") (pin "1") (pinfunction "1_1") (pintype "passive"))
      (node (ref "S1") (pin "1") (pinfunction "P_1") (pintype "passive"))
      (node (ref "U1") (pin "11") (pinfunction "GND_11") (pintype "power_in"))
      (node (ref "U1") (pin "32") (pinfunction "GND1_32") (pintype "power_in"))
      (node (ref "U1") (pin "62") (pinfunction "GND2_62") (pintype "power_in"))
      (node (ref "U1") (pin "81") (pinfunction "GND3_81") (pintype "power_in"))
      (node (ref "U1") (pin "99") (pinfunction "AGND_99") (pintype "power_in"))
      (node (ref "U2") (pin "16") (pinfunction "VSS_16") (pintype "output"))
    )
    (net (code "72") (name "LEDB") (class "Default")
      (node (ref "R3") (pin "1") (pinfunction "1_1") (pintype "passive"))
      (node (ref "U1") (pin "7") (pinfunction "(OC3C/INT5)PE5_7") (pintype "bidirectional"))
    )
    (net (code "73") (name "LEDG") (class "Default")
      (node (ref "R13") (pin "1") (pinfunction "1_1") (pintype "passive"))
      (node (ref "U1") (pin "1") (pinfunction "(OC0B)PG5_1") (pintype "bidirectional"))
    )
    (net (code "74") (name "LEDR") (class "Default")
      (node (ref "R2") (pin "1") (pinfunction "1_1") (pintype "passive"))
      (node (ref "U1") (pin "6") (pinfunction "(OC3B/INT4)PE4_6") (pintype "bidirectional"))
    )
    (net (code "75") (name "LEFT") (class "Default")
      (node (ref "IC4") (pin "67") (pinfunction "FB8MC9_67") (pintype "bidirectional"))
      (node (ref "J2") (pin "3") (pinfunction "3_3") (pintype "passive"))
    )
    (net (code "76") (name "LE_IL") (class "Default")
      (node (ref "IC5") (pin "11") (pinfunction "C_11") (pintype "input"))
      (node (ref "U1") (pin "5") (pinfunction "(OC3A/AIN1)PE3_5") (pintype "bidirectional"))
    )
    (net (code "77") (name "LE_OL") (class "Default")
      (node (ref "IC4") (pin "72") (pinfunction "FB8MC15_72") (pintype "bidirectional"))
      (node (ref "IC9") (pin "11") (pinfunction "C_11") (pintype "input"))
    )
    (net (code "78") (name "MISO") (class "Default")
      (node (ref "JP6") (pin "1") (pinfunction "1_1") (pintype "passive"))
      (node (ref "R1") (pin "1") (pinfunction "1_1") (pintype "passive"))
      (node (ref "U1") (pin "22") (pinfunction "(MISO/PCINT3)PB3_22") (pintype "bidirectional"))
    )
    (net (code "79") (name "MOSI") (class "Default")
      (node (ref "JP6") (pin "4") (pinfunction "4_4") (pintype "passive"))
      (node (ref "R17") (pin "1") (pinfunction "1_1") (pintype "passive"))
      (node (ref "U1") (pin "21") (pinfunction "(MOSI/PCINT2)PB2_21") (pintype "bidirectional"))
    )
    (net (code "80") (name "Net-(IC4-FB5MC8)") (class "Default")
      (node (ref "IC4") (pin "39") (pinfunction "FB5MC8_39") (pintype "bidirectional"))
      (node (ref "SJ2") (pin "1") (pinfunction "1_1") (pintype "passive"))
    )
    (net (code "81") (name "Net-(IC4-FB8MC17)") (class "Default")
      (node (ref "IC4") (pin "73") (pinfunction "FB8MC17_73") (pintype "bidirectional"))
      (node (ref "PAD6") (pin "1") (pinfunction "P_1") (pintype "passive"))
    )
    (net (code "82") (name "Net-(IC4-GCK3)") (class "Default")
      (node (ref "IC4") (pin "27") (pinfunction "GCK3_27") (pintype "bidirectional"))
      (node (ref "PAD1") (pin "1") (pinfunction "P_1") (pintype "passive"))
    )
    (net (code "83") (name "Net-(IC6A-I)") (class "Default")
      (node (ref "IC6") (pin "2") (pinfunction "I_2") (pintype "input"))
      (node (ref "R17") (pin "2") (pinfunction "2_2") (pintype "passive"))
    )
    (net (code "84") (name "Net-(IC6B-I)") (class "Default")
      (node (ref "IC6") (pin "5") (pinfunction "I_5") (pintype "input"))
      (node (ref "R18") (pin "2") (pinfunction "2_2") (pintype "passive"))
    )
    (net (code "85") (name "Net-(IC6C-I)") (class "Default")
      (node (ref "IC6") (pin "9") (pinfunction "I_9") (pintype "input"))
      (node (ref "R21") (pin "2") (pinfunction "2_2") (pintype "passive"))
    )
    (net (code "86") (name "Net-(IC6D-O)") (class "Default")
      (node (ref "IC6") (pin "11") (pinfunction "O_11") (pintype "tri_state"))
      (node (ref "R1") (pin "2") (pinfunction "2_2") (pintype "passive"))
    )
    (net (code "87") (name "Net-(IC7-DTR)") (class "Default")
      (node (ref "C9") (pin "2") (pinfunction "2_2") (pintype "passive"))
      (node (ref "IC7") (pin "13") (pinfunction "DTR_13") (pintype "bidirectional"))
      (node (ref "R26") (pin "1") (pinfunction "1_1") (pintype "passive"))
    )
    (net (code "88") (name "Net-(IC7-RX)") (class "Default")
      (node (ref "IC7") (pin "3") (pinfunction "RX_3") (pintype "bidirectional"))
      (node (ref "R23") (pin "2") (pinfunction "2_2") (pintype "passive"))
    )
    (net (code "89") (name "Net-(IC7-TX)") (class "Default")
      (node (ref "IC7") (pin "2") (pinfunction "TX_2") (pintype "bidirectional"))
      (node (ref "R22") (pin "2") (pinfunction "2_2") (pintype "passive"))
    )
    (net (code "90") (name "Net-(IC7-V3)") (class "Default")
      (node (ref "C8") (pin "2") (pinfunction "2_2") (pintype "passive"))
      (node (ref "IC7") (pin "4") (pinfunction "V3_4") (pintype "bidirectional"))
    )
    (net (code "91") (name "Net-(IC7-XI)") (class "Default")
      (node (ref "C20") (pin "2") (pinfunction "2_2") (pintype "passive"))
      (node (ref "IC7") (pin "7") (pinfunction "XI_7") (pintype "bidirectional"))
      (node (ref "Q2") (pin "3") (pinfunction "2_3") (pintype "passive"))
      (node (ref "R27") (pin "2") (pinfunction "2_2") (pintype "passive"))
    )
    (net (code "92") (name "Net-(IC7-XO)") (class "Default")
      (node (ref "C21") (pin "2") (pinfunction "2_2") (pintype "passive"))
      (node (ref "IC7") (pin "8") (pinfunction "XO_8") (pintype "bidirectional"))
      (node (ref "Q2") (pin "1") (pinfunction "1_1") (pintype "passive"))
      (node (ref "R27") (pin "1") (pinfunction "1_1") (pintype "passive"))
    )
    (net (code "93") (name "Net-(J1-D+)") (class "Default")
      (node (ref "J1") (pin "3") (pinfunction "D+_3") (pintype "bidirectional"))
      (node (ref "R29") (pin "2") (pinfunction "2_2") (pintype "passive"))
    )
    (net (code "94") (name "Net-(J1-D-)") (class "Default")
      (node (ref "J1") (pin "2") (pinfunction "D-_2") (pintype "bidirectional"))
      (node (ref "R28") (pin "2") (pinfunction "2_2") (pintype "passive"))
    )
    (net (code "95") (name "Net-(LED2-PadA)") (class "Default")
      (node (ref "LED2") (pin "A") (pinfunction "A_A") (pintype "passive"))
      (node (ref "R11") (pin "2") (pinfunction "2_2") (pintype "passive"))
    )
    (net (code "96") (name "Net-(LED3A-A)") (class "Default")
      (node (ref "LED3") (pin "P6") (pinfunction "A_P6") (pintype "passive"))
      (node (ref "R3") (pin "2") (pinfunction "2_2") (pintype "passive"))
    )
    (net (code "97") (name "Net-(LED3B-A)") (class "Default")
      (node (ref "LED3") (pin "P5") (pinfunction "A_P5") (pintype "passive"))
      (node (ref "R13") (pin "2") (pinfunction "2_2") (pintype "passive"))
    )
    (net (code "98") (name "Net-(LED3C-A)") (class "Default")
      (node (ref "LED3") (pin "P4") (pinfunction "A_P4") (pintype "passive"))
      (node (ref "R2") (pin "2") (pinfunction "2_2") (pintype "passive"))
    )
    (net (code "99") (name "Net-(MICRO_SD1-DAT0)") (class "Default")
      (node (ref "MICRO_SD1") (pin "7") (pinfunction "DAT0_7") (pintype "bidirectional"))
      (node (ref "R20") (pin "2") (pinfunction "2_2") (pintype "passive"))
    )
    (net (code "100") (name "Net-(PAD2-P)") (class "Default")
      (node (ref "PAD2") (pin "1") (pinfunction "P_1") (pintype "passive"))
      (node (ref "U1") (pin "27") (pinfunction "PH7(T4)_27") (pintype "bidirectional"))
    )
    (net (code "101") (name "Net-(PAD3-P)") (class "Default")
      (node (ref "PAD3") (pin "1") (pinfunction "P_1") (pintype "passive"))
      (node (ref "U1") (pin "28") (pinfunction "(TOSC2)PG3_28") (pintype "bidirectional"))
    )
    (net (code "102") (name "Net-(Q1-2)") (class "Default")
      (node (ref "C16") (pin "2") (pinfunction "2_2") (pintype "passive"))
      (node (ref "Q1") (pin "3") (pinfunction "2_3") (pintype "passive"))
      (node (ref "R19") (pin "2") (pinfunction "2_2") (pintype "passive"))
      (node (ref "U1") (pin "33") (pinfunction "XTAL2_33") (pintype "output"))
    )
    (net (code "103") (name "Net-(U1-XTAL1)") (class "Default")
      (node (ref "C17") (pin "2") (pinfunction "2_2") (pintype "passive"))
      (node (ref "Q1") (pin "1") (pinfunction "1_1") (pintype "passive"))
      (node (ref "R19") (pin "1") (pinfunction "1_1") (pintype "passive"))
      (node (ref "U1") (pin "34") (pinfunction "XTAL1_34") (pintype "input"))
    )
    (net (code "104") (name "O0") (class "Default")
      (node (ref "IC5") (pin "9") (pinfunction "8D_9") (pintype "input"))
      (node (ref "U1") (pin "89") (pinfunction "PK0(ADC8/PCINT16)_89") (pintype "bidirectional"))
    )
    (net (code "105") (name "O1") (class "Default")
      (node (ref "IC5") (pin "8") (pinfunction "7D_8") (pintype "input"))
      (node (ref "U1") (pin "88") (pinfunction "PK1(ADC9/PCINT17)_88") (pintype "bidirectional"))
    )
    (net (code "106") (name "O2") (class "Default")
      (node (ref "IC5") (pin "7") (pinfunction "6D_7") (pintype "input"))
      (node (ref "U1") (pin "87") (pinfunction "PK2(ADC10/PCINT18)_87") (pintype "bidirectional"))
    )
    (net (code "107") (name "O3") (class "Default")
      (node (ref "IC5") (pin "6") (pinfunction "5D_6") (pintype "input"))
      (node (ref "U1") (pin "86") (pinfunction "PK3(ADC11/PCINT19)_86") (pintype "bidirectional"))
    )
    (net (code "108") (name "O4") (class "Default")
      (node (ref "IC5") (pin "5") (pinfunction "4D_5") (pintype "input"))
      (node (ref "U1") (pin "85") (pinfunction "PK4(ADC12/PCINT20)_85") (pintype "bidirectional"))
    )
    (net (code "109") (name "O5") (class "Default")
      (node (ref "IC5") (pin "4") (pinfunction "3D_4") (pintype "input"))
      (node (ref "U1") (pin "84") (pinfunction "PK5(ADC13/PCINT21)_84") (pintype "bidirectional"))
    )
    (net (code "110") (name "O6") (class "Default")
      (node (ref "IC5") (pin "3") (pinfunction "2D_3") (pintype "input"))
      (node (ref "U1") (pin "83") (pinfunction "PK6(ADC14/PCINT22)_83") (pintype "bidirectional"))
    )
    (net (code "111") (name "O7") (class "Default")
      (node (ref "IC5") (pin "2") (pinfunction "1D_2") (pintype "input"))
      (node (ref "U1") (pin "82") (pinfunction "PK7(ADC15/PCINT23)_82") (pintype "bidirectional"))
    )
    (net (code "112") (name "OE_OL") (class "Default")
      (node (ref "IC9") (pin "1") (pinfunction "OC_1") (pintype "input"))
      (node (ref "U1") (pin "13") (pinfunction "PH1(TXD2)_13") (pintype "bidirectional"))
    )
    (net (code "113") (name "PAGE_A8") (class "Default")
      (node (ref "IC4") (pin "80") (pinfunction "FB6MC11_80") (pintype "bidirectional"))
      (node (ref "U1") (pin "41") (pinfunction "PL6_41") (pintype "bidirectional"))
    )
    (net (code "114") (name "RD+") (class "Default")
      (node (ref "IC7") (pin "5") (pinfunction "D+_5") (pintype "bidirectional"))
      (node (ref "R29") (pin "1") (pinfunction "1_1") (pintype "passive"))
    )
    (net (code "115") (name "RD-") (class "Default")
      (node (ref "IC7") (pin "6") (pinfunction "D-_6") (pintype "bidirectional"))
      (node (ref "R28") (pin "1") (pinfunction "1_1") (pintype "passive"))
    )
    (net (code "116") (name "RESET") (class "Default")
      (node (ref "C5") (pin "2") (pinfunction "2_2") (pintype "passive"))
      (node (ref "C9") (pin "1") (pinfunction "1_1") (pintype "passive"))
      (node (ref "D1") (pin "A") (pinfunction "A_A") (pintype "passive"))
      (node (ref "JP6") (pin "5") (pinfunction "5_5") (pintype "passive"))
      (node (ref "R15") (pin "1") (pinfunction "1_1") (pintype "passive"))
      (node (ref "S1") (pin "2") (pinfunction "S_2") (pintype "passive"))
      (node (ref "U1") (pin "30") (pinfunction "RESET_30") (pintype "input"))
    )
    (net (code "117") (name "RIGHT") (class "Default")
      (node (ref "IC4") (pin "68") (pinfunction "FB8MC11_68") (pintype "bidirectional"))
      (node (ref "J2") (pin "4") (pinfunction "4_4") (pintype "passive"))
    )
    (net (code "118") (name "ROM_WR_EN") (class "Default")
      (node (ref "IC4") (pin "79") (pinfunction "FB6MC9_79") (pintype "bidirectional"))
      (node (ref "U1") (pin "36") (pinfunction "PL1(ICP5)_36") (pintype "bidirectional"))
    )
    (net (code "119") (name "RST_CTRL_REG") (class "Default")
      (node (ref "IC4") (pin "82") (pinfunction "FB6MC14_82") (pintype "bidirectional"))
      (node (ref "U1") (pin "26") (pinfunction "(OC0A/OC1C/PCINT7)PB7_26") (pintype "bidirectional"))
    )
    (net (code "120") (name "RST_DATA_REG") (class "Default")
      (node (ref "IC4") (pin "81") (pinfunction "FB6MC12_81") (pintype "bidirectional"))
      (node (ref "U1") (pin "63") (pinfunction "PJ0(RXD3/PCINT9)_63") (pintype "bidirectional"))
    )
    (net (code "121") (name "RX0") (class "Default")
      (node (ref "R23") (pin "1") (pinfunction "1_1") (pintype "passive"))
      (node (ref "U1") (pin "3") (pinfunction "(TXD0)PE1_3") (pintype "bidirectional"))
    )
    (net (code "122") (name "SCK_LLS") (class "Default")
      (node (ref "IC6") (pin "6") (pinfunction "O_6") (pintype "tri_state"))
      (node (ref "MICRO_SD1") (pin "5") (pinfunction "CLK_5") (pintype "bidirectional"))
    )
    (net (code "123") (name "SCLK") (class "Default")
      (node (ref "JP6") (pin "3") (pinfunction "3_3") (pintype "passive"))
      (node (ref "R18") (pin "1") (pinfunction "1_1") (pintype "passive"))
      (node (ref "U1") (pin "20") (pinfunction "(SCK/PCINT1)PB1_20") (pintype "bidirectional"))
    )
    (net (code "124") (name "SD_LED") (class "Default")
      (node (ref "LED2") (pin "C") (pinfunction "C_C") (pintype "passive"))
      (node (ref "U1") (pin "37") (pinfunction "PL2(T5)_37") (pintype "bidirectional"))
    )
    (net (code "125") (name "SEL_128CHARS") (class "Default")
      (node (ref "IC4") (pin "78") (pinfunction "FB6MC8_78") (pintype "bidirectional"))
      (node (ref "U1") (pin "35") (pinfunction "PL0(ICP4)_35") (pintype "bidirectional"))
    )
    (net (code "126") (name "SPARE1") (class "Default")
      (node (ref "IC4") (pin "77") (pinfunction "FB6MC6_77") (pintype "bidirectional"))
      (node (ref "U1") (pin "38") (pinfunction "PL3(OC5A)_38") (pintype "bidirectional"))
    )
    (net (code "127") (name "SS_SD") (class "Default")
      (node (ref "R21") (pin "1") (pinfunction "1_1") (pintype "passive"))
      (node (ref "U1") (pin "19") (pinfunction "(SS/PCINT0)PB0_19") (pintype "bidirectional"))
    )
    (net (code "128") (name "TCK") (class "Default")
      (node (ref "IC4") (pin "48") (pinfunction "TCK_48") (pintype "passive"))
      (node (ref "JP3") (pin "1") (pinfunction "1_1") (pintype "passive"))
      (node (ref "R7") (pin "2") (pinfunction "2_2") (pintype "passive"))
      (node (ref "R8") (pin "2") (pinfunction "2_2") (pintype "passive"))
    )
    (net (code "129") (name "TCK'") (class "Default")
      (node (ref "R7") (pin "1") (pinfunction "1_1") (pintype "passive"))
      (node (ref "U1") (pin "24") (pinfunction "(OC1A/PCINT5)PB5_24") (pintype "bidirectional"))
    )
    (net (code "130") (name "TDI") (class "Default")
      (node (ref "IC4") (pin "45") (pinfunction "TDI_45") (pintype "passive"))
      (node (ref "JP3") (pin "3") (pinfunction "3_3") (pintype "passive"))
      (node (ref "R5") (pin "2") (pinfunction "2_2") (pintype "passive"))
      (node (ref "R9") (pin "2") (pinfunction "2_2") (pintype "passive"))
    )
    (net (code "131") (name "TDI'") (class "Default")
      (node (ref "R5") (pin "1") (pinfunction "1_1") (pintype "passive"))
      (node (ref "U1") (pin "18") (pinfunction "PH6(OC2B)_18") (pintype "bidirectional"))
    )
    (net (code "132") (name "TDO") (class "Default")
      (node (ref "IC4") (pin "83") (pinfunction "TDO_83") (pintype "passive"))
      (node (ref "JP3") (pin "2") (pinfunction "2_2") (pintype "passive"))
      (node (ref "R6") (pin "2") (pinfunction "2_2") (pintype "passive"))
    )
    (net (code "133") (name "TDO'") (class "Default")
      (node (ref "R6") (pin "1") (pinfunction "1_1") (pintype "passive"))
      (node (ref "U1") (pin "17") (pinfunction "PH5(OC4C)_17") (pintype "bidirectional"))
    )
    (net (code "134") (name "TMS") (class "Default")
      (node (ref "IC4") (pin "47") (pinfunction "TMS_47") (pintype "passive"))
      (node (ref "JP3") (pin "4") (pinfunction "4_4") (pintype "passive"))
      (node (ref "R10") (pin "2") (pinfunction "2_2") (pintype "passive"))
      (node (ref "R4") (pin "2") (pinfunction "2_2") (pintype "passive"))
    )
    (net (code "135") (name "TMS'") (class "Default")
      (node (ref "R4") (pin "1") (pinfunction "1_1") (pintype "passive"))
      (node (ref "U1") (pin "23") (pinfunction "(OC2A/PCINT4)PB4_23") (pintype "bidirectional"))
    )
    (net (code "136") (name "TX0") (class "Default")
      (node (ref "R22") (pin "1") (pinfunction "1_1") (pintype "passive"))
      (node (ref "U1") (pin "2") (pinfunction "(RXD0/PCIN8)PE0_2") (pintype "bidirectional"))
    )
    (net (code "137") (name "UP") (class "Default")
      (node (ref "IC4") (pin "65") (pinfunction "FB8MC6_65") (pintype "bidirectional"))
      (node (ref "J2") (pin "1") (pinfunction "1_1") (pintype "passive"))
    )
    (net (code "138") (name "VCC") (class "Default")
      (node (ref "C1") (pin "1") (pinfunction "1_1") (pintype "passive"))
      (node (ref "C13") (pin "1") (pinfunction "1_1") (pintype "passive"))
      (node (ref "C14") (pin "1") (pinfunction "1_1") (pintype "passive"))
      (node (ref "C15") (pin "1") (pinfunction "1_1") (pintype "passive"))
      (node (ref "C19") (pin "1") (pinfunction "1_1") (pintype "passive"))
      (node (ref "C2") (pin "1") (pinfunction "1_1") (pintype "passive"))
      (node (ref "C3") (pin "1") (pinfunction "1_1") (pintype "passive"))
      (node (ref "D1") (pin "C") (pinfunction "C_C") (pintype "passive"))
      (node (ref "IC1") (pin "2") (pinfunction "VO_2") (pintype "passive"))
      (node (ref "IC2") (pin "3") (pinfunction "VIN_3") (pintype "input"))
      (node (ref "IC3") (pin "12") (pinfunction "I_12") (pintype "input"))
      (node (ref "IC3") (pin "13") (pinfunction "OE_13") (pintype "input"))
      (node (ref "IC3") (pin "2") (pinfunction "I_2") (pintype "input"))
      (node (ref "IC3") (pin "5") (pinfunction "I_5") (pintype "input"))
      (node (ref "IC7") (pin "16") (pinfunction "VCC_16") (pintype "bidirectional"))
      (node (ref "J1") (pin "1") (pinfunction "VBUS_1") (pintype "power_in"))
      (node (ref "JP6") (pin "2") (pinfunction "2_2") (pintype "passive"))
      (node (ref "R11") (pin "1") (pinfunction "1_1") (pintype "passive"))
      (node (ref "R15") (pin "2") (pinfunction "2_2") (pintype "passive"))
      (node (ref "SJ1") (pin "2") (pinfunction "2_2") (pintype "passive"))
      (node (ref "U1") (pin "10") (pinfunction "VCC_10") (pintype "power_in"))
      (node (ref "U1") (pin "100") (pinfunction "AVCC_100") (pintype "power_in"))
      (node (ref "U1") (pin "31") (pinfunction "VCC1_31") (pintype "power_in"))
      (node (ref "U1") (pin "61") (pinfunction "VCC2_61") (pintype "power_in"))
      (node (ref "U1") (pin "80") (pinfunction "VCC3_80") (pintype "power_in"))
      (node (ref "U2") (pin "32") (pinfunction "VCC_32") (pintype "power_in"))
    )
    (net (code "139") (name "unconnected-(IC3D-O-Pad11)") (class "Default")
      (node (ref "IC3") (pin "11") (pinfunction "O_11") (pintype "tri_state"))
    )
    (net (code "140") (name "unconnected-(IC7-CTS-Pad9)") (class "Default")
      (node (ref "IC7") (pin "9") (pinfunction "CTS_9") (pintype "bidirectional"))
    )
    (net (code "141") (name "unconnected-(IC7-DCD-Pad12)") (class "Default")
      (node (ref "IC7") (pin "12") (pinfunction "DCD_12") (pintype "bidirectional"))
    )
    (net (code "142") (name "unconnected-(IC7-DSR-Pad10)") (class "Default")
      (node (ref "IC7") (pin "10") (pinfunction "DSR_10") (pintype "bidirectional"))
    )
    (net (code "143") (name "unconnected-(IC7-RI-Pad11)") (class "Default")
      (node (ref "IC7") (pin "11") (pinfunction "RI_11") (pintype "bidirectional"))
    )
    (net (code "144") (name "unconnected-(IC7-RS232-Pad15)") (class "Default")
      (node (ref "IC7") (pin "15") (pinfunction "RS232_15") (pintype "bidirectional"))
    )
    (net (code "145") (name "unconnected-(IC7-RTS-Pad14)") (class "Default")
      (node (ref "IC7") (pin "14") (pinfunction "RTS_14") (pintype "bidirectional"))
    )
    (net (code "146") (name "unconnected-(J1-ID-Pad4)") (class "Default")
      (node (ref "J1") (pin "4") (pinfunction "ID_4") (pintype "bidirectional"))
    )
    (net (code "147") (name "unconnected-(J2-Pad5)") (class "Default")
      (node (ref "J2") (pin "5") (pinfunction "5_5") (pintype "passive"))
    )
    (net (code "148") (name "unconnected-(J2-Pad7)") (class "Default")
      (node (ref "J2") (pin "7") (pinfunction "7_7") (pintype "passive"))
    )
    (net (code "149") (name "unconnected-(J2-Pad9)") (class "Default")
      (node (ref "J2") (pin "9") (pinfunction "9_9") (pintype "passive"))
    )
    (net (code "150") (name "unconnected-(MICRO_SD1-CD-PadCD1)") (class "Default")
      (node (ref "MICRO_SD1") (pin "CD1") (pinfunction "CD_CD1") (pintype "passive"))
    )
    (net (code "151") (name "unconnected-(MICRO_SD1-DAT1-Pad8)") (class "Default")
      (node (ref "MICRO_SD1") (pin "8") (pinfunction "DAT1_8") (pintype "bidirectional"))
    )
    (net (code "152") (name "unconnected-(MICRO_SD1-DAT2-Pad1)") (class "Default")
      (node (ref "MICRO_SD1") (pin "1") (pinfunction "DAT2_1") (pintype "bidirectional"))
    )
    (net (code "153") (name "unconnected-(U1-(CLKO{slash}ICP3{slash}INT7)PE7-Pad9)") (class "Default")
      (node (ref "U1") (pin "9") (pinfunction "(CLKO/ICP3/INT7)PE7_9") (pintype "bidirectional"))
    )
    (net (code "154") (name "unconnected-(U1-(ICP1)PD4-Pad47)") (class "Default")
      (node (ref "U1") (pin "47") (pinfunction "(ICP1)PD4_47") (pintype "bidirectional"))
    )
    (net (code "155") (name "unconnected-(U1-(T1)PD6-Pad49)") (class "Default")
      (node (ref "U1") (pin "49") (pinfunction "(T1)PD6_49") (pintype "bidirectional"))
    )
    (net (code "156") (name "unconnected-(U1-(T3{slash}INT6)PE6-Pad8)") (class "Default")
      (node (ref "U1") (pin "8") (pinfunction "(T3/INT6)PE6_8") (pintype "bidirectional"))
    )
    (net (code "157") (name "unconnected-(U1-(TOSC1)PG4-Pad29)") (class "Default")
      (node (ref "U1") (pin "29") (pinfunction "(TOSC1)PG4_29") (pintype "bidirectional"))
    )
    (net (code "158") (name "unconnected-(U1-(XCK0{slash}AIN0)PE2-Pad4)") (class "Default")
      (node (ref "U1") (pin "4") (pinfunction "(XCK0/AIN0)PE2_4") (pintype "bidirectional"))
    )
    (net (code "159") (name "unconnected-(U1-(XCK1)PD5-Pad48)") (class "Default")
      (node (ref "U1") (pin "48") (pinfunction "(XCK1)PD5_48") (pintype "bidirectional"))
    )
    (net (code "160") (name "unconnected-(U1-PH2(XCK2)-Pad14)") (class "Default")
      (node (ref "U1") (pin "14") (pinfunction "PH2(XCK2)_14") (pintype "bidirectional"))
    )
    (net (code "161") (name "unconnected-(U1-PJ2(XCK3{slash}PCINT11)-Pad65)") (class "Default")
      (node (ref "U1") (pin "65") (pinfunction "PJ2(XCK3/PCINT11)_65") (pintype "bidirectional"))
    )
    (net (code "162") (name "unconnected-(U1-PJ3(PCINT12)-Pad66)") (class "Default")
      (node (ref "U1") (pin "66") (pinfunction "PJ3(PCINT12)_66") (pintype "bidirectional"))
    )
    (net (code "163") (name "unconnected-(U1-PJ4(PCINT13)-Pad67)") (class "Default")
      (node (ref "U1") (pin "67") (pinfunction "PJ4(PCINT13)_67") (pintype "bidirectional"))
    )
    (net (code "164") (name "{slash}BUSAK") (class "Default")
      (node (ref "18A") (pin "1") (pinfunction "P_1") (pintype "passive"))
    )
    (net (code "165") (name "{slash}BUSRQ") (class "Default")
      (node (ref "20A") (pin "1") (pinfunction "P_1") (pintype "passive"))
    )
    (net (code "166") (name "{slash}CLOCK") (class "Default")
      (node (ref "6B") (pin "1") (pinfunction "P_1") (pintype "passive"))
      (node (ref "IC4") (pin "22") (pinfunction "GCK1_22") (pintype "bidirectional"))
    )
    (net (code "167") (name "{slash}HALT") (class "Default")
      (node (ref "13A") (pin "1") (pinfunction "P_1") (pintype "passive"))
      (node (ref "SJ2") (pin "2") (pinfunction "2_2") (pintype "passive"))
    )
    (net (code "168") (name "{slash}IORQ") (class "Default")
      (node (ref "15A") (pin "1") (pinfunction "P_1") (pintype "passive"))
      (node (ref "IC4") (pin "43") (pinfunction "FB5MC14_43") (pintype "bidirectional"))
    )
    (net (code "169") (name "{slash}M1") (class "Default")
      (node (ref "22A") (pin "1") (pinfunction "P_1") (pintype "passive"))
      (node (ref "IC4") (pin "61") (pinfunction "FB7MC17_61") (pintype "bidirectional"))
    )
    (net (code "170") (name "{slash}MEM_CE") (class "Default")
      (node (ref "IC4") (pin "97") (pinfunction "FB4MC17_97") (pintype "bidirectional"))
      (node (ref "U1") (pin "50") (pinfunction "(T0)PD7_50") (pintype "bidirectional"))
      (node (ref "U2") (pin "22") (pinfunction "CE_22") (pintype "input"))
    )
    (net (code "171") (name "{slash}MEM_OE") (class "Default")
      (node (ref "IC4") (pin "12") (pinfunction "FB1MC3_12") (pintype "bidirectional"))
      (node (ref "U1") (pin "52") (pinfunction "(RD)PG1_52") (pintype "bidirectional"))
      (node (ref "U2") (pin "24") (pinfunction "OE_24") (pintype "input"))
    )
    (net (code "172") (name "{slash}MREQ") (class "Default")
      (node (ref "14A") (pin "1") (pinfunction "P_1") (pintype "passive"))
      (node (ref "IC4") (pin "41") (pinfunction "FB5MC11_41") (pintype "bidirectional"))
    )
    (net (code "173") (name "{slash}NMI") (class "Default")
      (node (ref "12A") (pin "1") (pinfunction "P_1") (pintype "passive"))
      (node (ref "IC4") (pin "36") (pinfunction "FB5MC5_36") (pintype "bidirectional"))
    )
    (net (code "174") (name "{slash}OE_CTRL_CLOCK") (class "Default")
      (node (ref "IC3") (pin "10") (pinfunction "OE_10") (pintype "input"))
      (node (ref "IC4") (pin "10") (pinfunction "FB2MC17_10") (pintype "bidirectional"))
    )
    (net (code "175") (name "{slash}OE_IL") (class "Default")
      (node (ref "IC4") (pin "15") (pinfunction "FB1MC8_15") (pintype "bidirectional"))
      (node (ref "IC5") (pin "1") (pinfunction "OC_1") (pintype "input"))
    )
    (net (code "176") (name "{slash}OE_RAMCS") (class "Default")
      (node (ref "IC3") (pin "4") (pinfunction "OE_4") (pintype "input"))
      (node (ref "IC4") (pin "17") (pinfunction "FB1MC11_17") (pintype "bidirectional"))
    )
    (net (code "177") (name "{slash}OE_ROMCS") (class "Default")
      (node (ref "IC3") (pin "1") (pinfunction "OE_1") (pintype "input"))
      (node (ref "IC4") (pin "14") (pinfunction "FB1MC6_14") (pintype "bidirectional"))
    )
    (net (code "178") (name "{slash}RAMCS") (class "Default")
      (node (ref "2A") (pin "1") (pinfunction "P_1") (pintype "passive"))
      (node (ref "IC3") (pin "6") (pinfunction "O_6") (pintype "tri_state"))
    )
    (net (code "179") (name "{slash}RD") (class "Default")
      (node (ref "16A") (pin "1") (pinfunction "P_1") (pintype "passive"))
      (node (ref "IC4") (pin "49") (pinfunction "FB5MC17_49") (pintype "bidirectional"))
    )
    (net (code "180") (name "{slash}RESET") (class "Default")
      (node (ref "21A") (pin "1") (pinfunction "P_1") (pintype "passive"))
      (node (ref "IC4") (pin "71") (pinfunction "FB8MC14_71") (pintype "bidirectional"))
      (node (ref "U1") (pin "15") (pinfunction "PH3(OC4A)_15") (pintype "bidirectional"))
    )
    (net (code "181") (name "{slash}RFSH") (class "Default")
      (node (ref "23A") (pin "1") (pinfunction "P_1") (pintype "passive"))
      (node (ref "IC4") (pin "64") (pinfunction "FB8MC5_64") (pintype "bidirectional"))
    )
    (net (code "182") (name "{slash}ROMCS") (class "Default")
      (node (ref "23B") (pin "1") (pinfunction "P_1") (pintype "passive"))
      (node (ref "IC3") (pin "3") (pinfunction "O_3") (pintype "tri_state"))
    )
    (net (code "183") (name "{slash}WAIT") (class "Default")
      (node (ref "19A") (pin "1") (pinfunction "P_1") (pintype "passive"))
      (node (ref "IC4") (pin "56") (pinfunction "FB7MC11_56") (pintype "bidirectional"))
      (node (ref "U1") (pin "42") (pinfunction "PL7_42") (pintype "bidirectional"))
    )
    (net (code "184") (name "{slash}WR") (class "Default")
      (node (ref "17A") (pin "1") (pinfunction "P_1") (pintype "passive"))
      (node (ref "IC4") (pin "52") (pinfunction "FB7MC5_52") (pintype "bidirectional"))
    )
    (net (code "185") (name "{slash}WR'") (class "Default")
      (node (ref "IC4") (pin "13") (pinfunction "FB1MC5_13") (pintype "bidirectional"))
      (node (ref "U1") (pin "51") (pinfunction "(WR)PG0_51") (pintype "bidirectional"))
      (node (ref "U2") (pin "29") (pinfunction "WE_29") (pintype "input"))
    )
  )
)
